# lo_sec_subsystem.net
KiCad netlist of a schematic drawn in EAGLE
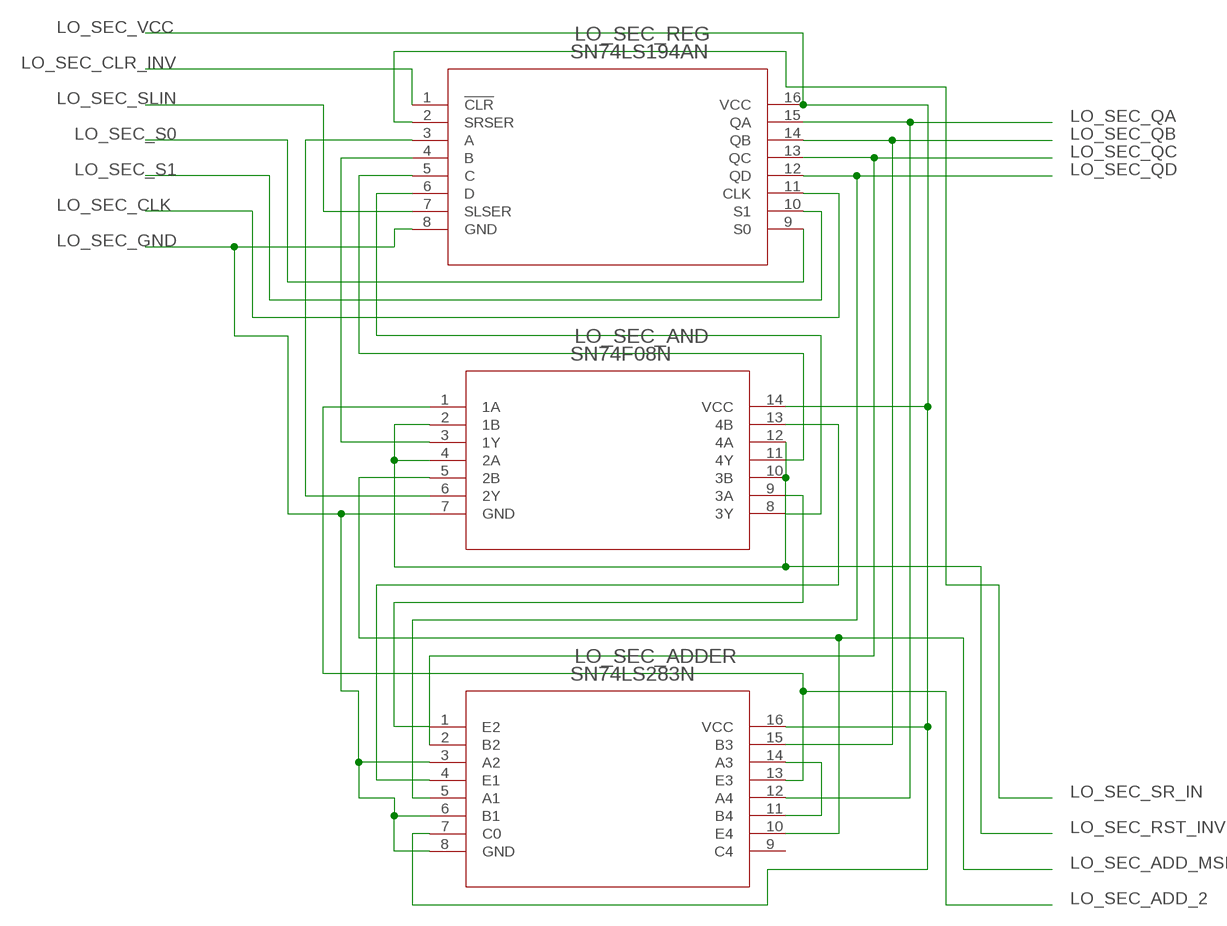
[diagram p0: schematic, sheet 1]

(export (version "E")
  (design (tool "Eeschema 10.0.6"))
  (components
    (comp (ref "LO_SEC_ADDER")
      (value "SN74LS283N")
      (footprint "eagle-import:N16")
      (fields
        (field (name "GENERIC_PART_NUMBER") "SN74LS283")
        (field (name "MANUFACTURER") "Texas Instruments")
      )
      (libsource (lib "eagle-import") (part "SN74LS283N"))
    )
    (comp (ref "LO_SEC_AND")
      (value "SN74F08N")
      (footprint "eagle-import:N14")
      (fields
        (field (name "GENERIC_PART_NUMBER") "SN74F08")
        (field (name "MANUFACTURER") "Texas Instruments")
      )
      (libsource (lib "eagle-import") (part "SN74F08N"))
    )
    (comp (ref "LO_SEC_REG")
      (value "SN74LS194AN")
      (footprint "eagle-import:N16")
      (fields
        (field (name "GENERIC_PART_NUMBER") "SN74LS194A")
        (field (name "MANUFACTURER") "Texas Instruments")
      )
      (libsource (lib "eagle-import") (part "SN74LS194AN"))
    )
  )
  (nets
    (net (code "1") (name "/LO_SEC_ADD_2") (class "Default")
      (node (ref "LO_SEC_ADDER") (pin "13") (pinfunction "E3_13") (pintype "output"))
      (node (ref "LO_SEC_AND") (pin "1") (pinfunction "1A_1") (pintype "input"))
    )
    (net (code "2") (name "/LO_SEC_ADD_MSB") (class "Default")
      (node (ref "LO_SEC_ADDER") (pin "10") (pinfunction "E4_10") (pintype "output"))
      (node (ref "LO_SEC_AND") (pin "5") (pinfunction "2B_5") (pintype "input"))
    )
    (net (code "3") (name "/LO_SEC_CLK") (class "Default")
      (node (ref "LO_SEC_REG") (pin "11") (pinfunction "CLK_11") (pintype "input"))
    )
    (net (code "4") (name "/LO_SEC_CLR_INV") (class "Default")
      (node (ref "LO_SEC_REG") (pin "1") (pinfunction "~{CLR}_1") (pintype "input"))
    )
    (net (code "5") (name "/LO_SEC_GND") (class "Default")
      (node (ref "LO_SEC_ADDER") (pin "3") (pinfunction "A2_3") (pintype "input"))
      (node (ref "LO_SEC_ADDER") (pin "6") (pinfunction "B1_6") (pintype "input"))
      (node (ref "LO_SEC_ADDER") (pin "8") (pinfunction "GND_8") (pintype "power_in"))
      (node (ref "LO_SEC_AND") (pin "7") (pinfunction "GND_7") (pintype "power_in"))
      (node (ref "LO_SEC_REG") (pin "8") (pinfunction "GND_8") (pintype "power_in"))
    )
    (net (code "6") (name "/LO_SEC_QA") (class "Default")
      (node (ref "LO_SEC_ADDER") (pin "12") (pinfunction "A4_12") (pintype "input"))
      (node (ref "LO_SEC_REG") (pin "15") (pinfunction "QA_15") (pintype "output"))
    )
    (net (code "7") (name "/LO_SEC_QB") (class "Default")
      (node (ref "LO_SEC_ADDER") (pin "15") (pinfunction "B3_15") (pintype "input"))
      (node (ref "LO_SEC_REG") (pin "14") (pinfunction "QB_14") (pintype "output"))
    )
    (net (code "8") (name "/LO_SEC_QC") (class "Default")
      (node (ref "LO_SEC_ADDER") (pin "2") (pinfunction "B2_2") (pintype "input"))
      (node (ref "LO_SEC_REG") (pin "13") (pinfunction "QC_13") (pintype "output"))
    )
    (net (code "9") (name "/LO_SEC_QD") (class "Default")
      (node (ref "LO_SEC_ADDER") (pin "5") (pinfunction "A1_5") (pintype "input"))
      (node (ref "LO_SEC_REG") (pin "12") (pinfunction "QD_12") (pintype "output"))
    )
    (net (code "10") (name "/LO_SEC_RST_INV") (class "Default")
      (node (ref "LO_SEC_AND") (pin "10") (pinfunction "3B_10") (pintype "input"))
      (node (ref "LO_SEC_AND") (pin "12") (pinfunction "4A_12") (pintype "input"))
      (node (ref "LO_SEC_AND") (pin "2") (pinfunction "1B_2") (pintype "input"))
      (node (ref "LO_SEC_AND") (pin "4") (pinfunction "2A_4") (pintype "input"))
    )
    (net (code "11") (name "/LO_SEC_S0") (class "Default")
      (node (ref "LO_SEC_REG") (pin "9") (pinfunction "S0_9") (pintype "input"))
    )
    (net (code "12") (name "/LO_SEC_S1") (class "Default")
      (node (ref "LO_SEC_REG") (pin "10") (pinfunction "S1_10") (pintype "input"))
    )
    (net (code "13") (name "/LO_SEC_SLIN") (class "Default")
      (node (ref "LO_SEC_REG") (pin "7") (pinfunction "SLSER_7") (pintype "input"))
    )
    (net (code "14") (name "/LO_SEC_SR_IN") (class "Default")
      (node (ref "LO_SEC_REG") (pin "2") (pinfunction "SRSER_2") (pintype "input"))
    )
    (net (code "15") (name "/LO_SEC_VCC") (class "Default")
      (node (ref "LO_SEC_ADDER") (pin "16") (pinfunction "VCC_16") (pintype "power_in"))
      (node (ref "LO_SEC_ADDER") (pin "7") (pinfunction "C0_7") (pintype "input"))
      (node (ref "LO_SEC_AND") (pin "14") (pinfunction "VCC_14") (pintype "power_in"))
      (node (ref "LO_SEC_REG") (pin "16") (pinfunction "VCC_16") (pintype "power_in"))
    )
    (net (code "16") (name "Net-(LO_SEC_ADDER-A3)") (class "Default")
      (node (ref "LO_SEC_ADDER") (pin "11") (pinfunction "B4_11") (pintype "input"))
      (node (ref "LO_SEC_ADDER") (pin "14") (pinfunction "A3_14") (pintype "input"))
    )
    (net (code "17") (name "Net-(LO_SEC_ADDER-E1)") (class "Default")
      (node (ref "LO_SEC_ADDER") (pin "4") (pinfunction "E1_4") (pintype "output"))
      (node (ref "LO_SEC_AND") (pin "13") (pinfunction "4B_13") (pintype "input"))
    )
    (net (code "18") (name "Net-(LO_SEC_ADDER-E2)") (class "Default")
      (node (ref "LO_SEC_ADDER") (pin "1") (pinfunction "E2_1") (pintype "output"))
      (node (ref "LO_SEC_AND") (pin "9") (pinfunction "3A_9") (pintype "input"))
    )
    (net (code "19") (name "Net-(LO_SEC_AND-1Y)") (class "Default")
      (node (ref "LO_SEC_AND") (pin "3") (pinfunction "1Y_3") (pintype "output"))
      (node (ref "LO_SEC_REG") (pin "4") (pinfunction "B_4") (pintype "input"))
    )
    (net (code "20") (name "Net-(LO_SEC_AND-2Y)") (class "Default")
      (node (ref "LO_SEC_AND") (pin "6") (pinfunction "2Y_6") (pintype "output"))
      (node (ref "LO_SEC_REG") (pin "3") (pinfunction "A_3") (pintype "input"))
    )
    (net (code "21") (name "Net-(LO_SEC_AND-3Y)") (class "Default")
      (node (ref "LO_SEC_AND") (pin "8") (pinfunction "3Y_8") (pintype "output"))
      (node (ref "LO_SEC_REG") (pin "6") (pinfunction "D_6") (pintype "input"))
    )
    (net (code "22") (name "Net-(LO_SEC_AND-4Y)") (class "Default")
      (node (ref "LO_SEC_AND") (pin "11") (pinfunction "4Y_11") (pintype "output"))
      (node (ref "LO_SEC_REG") (pin "5") (pinfunction "C_5") (pintype "input"))
    )
    (net (code "23") (name "unconnected-(LO_SEC_ADDER-C4-Pad9)") (class "Default")
      (node (ref "LO_SEC_ADDER") (pin "9") (pinfunction "C4_9") (pintype "input"))
    )
  )
)
